# controller.net
KiCad netlist of a schematic drawn in Altium Designer
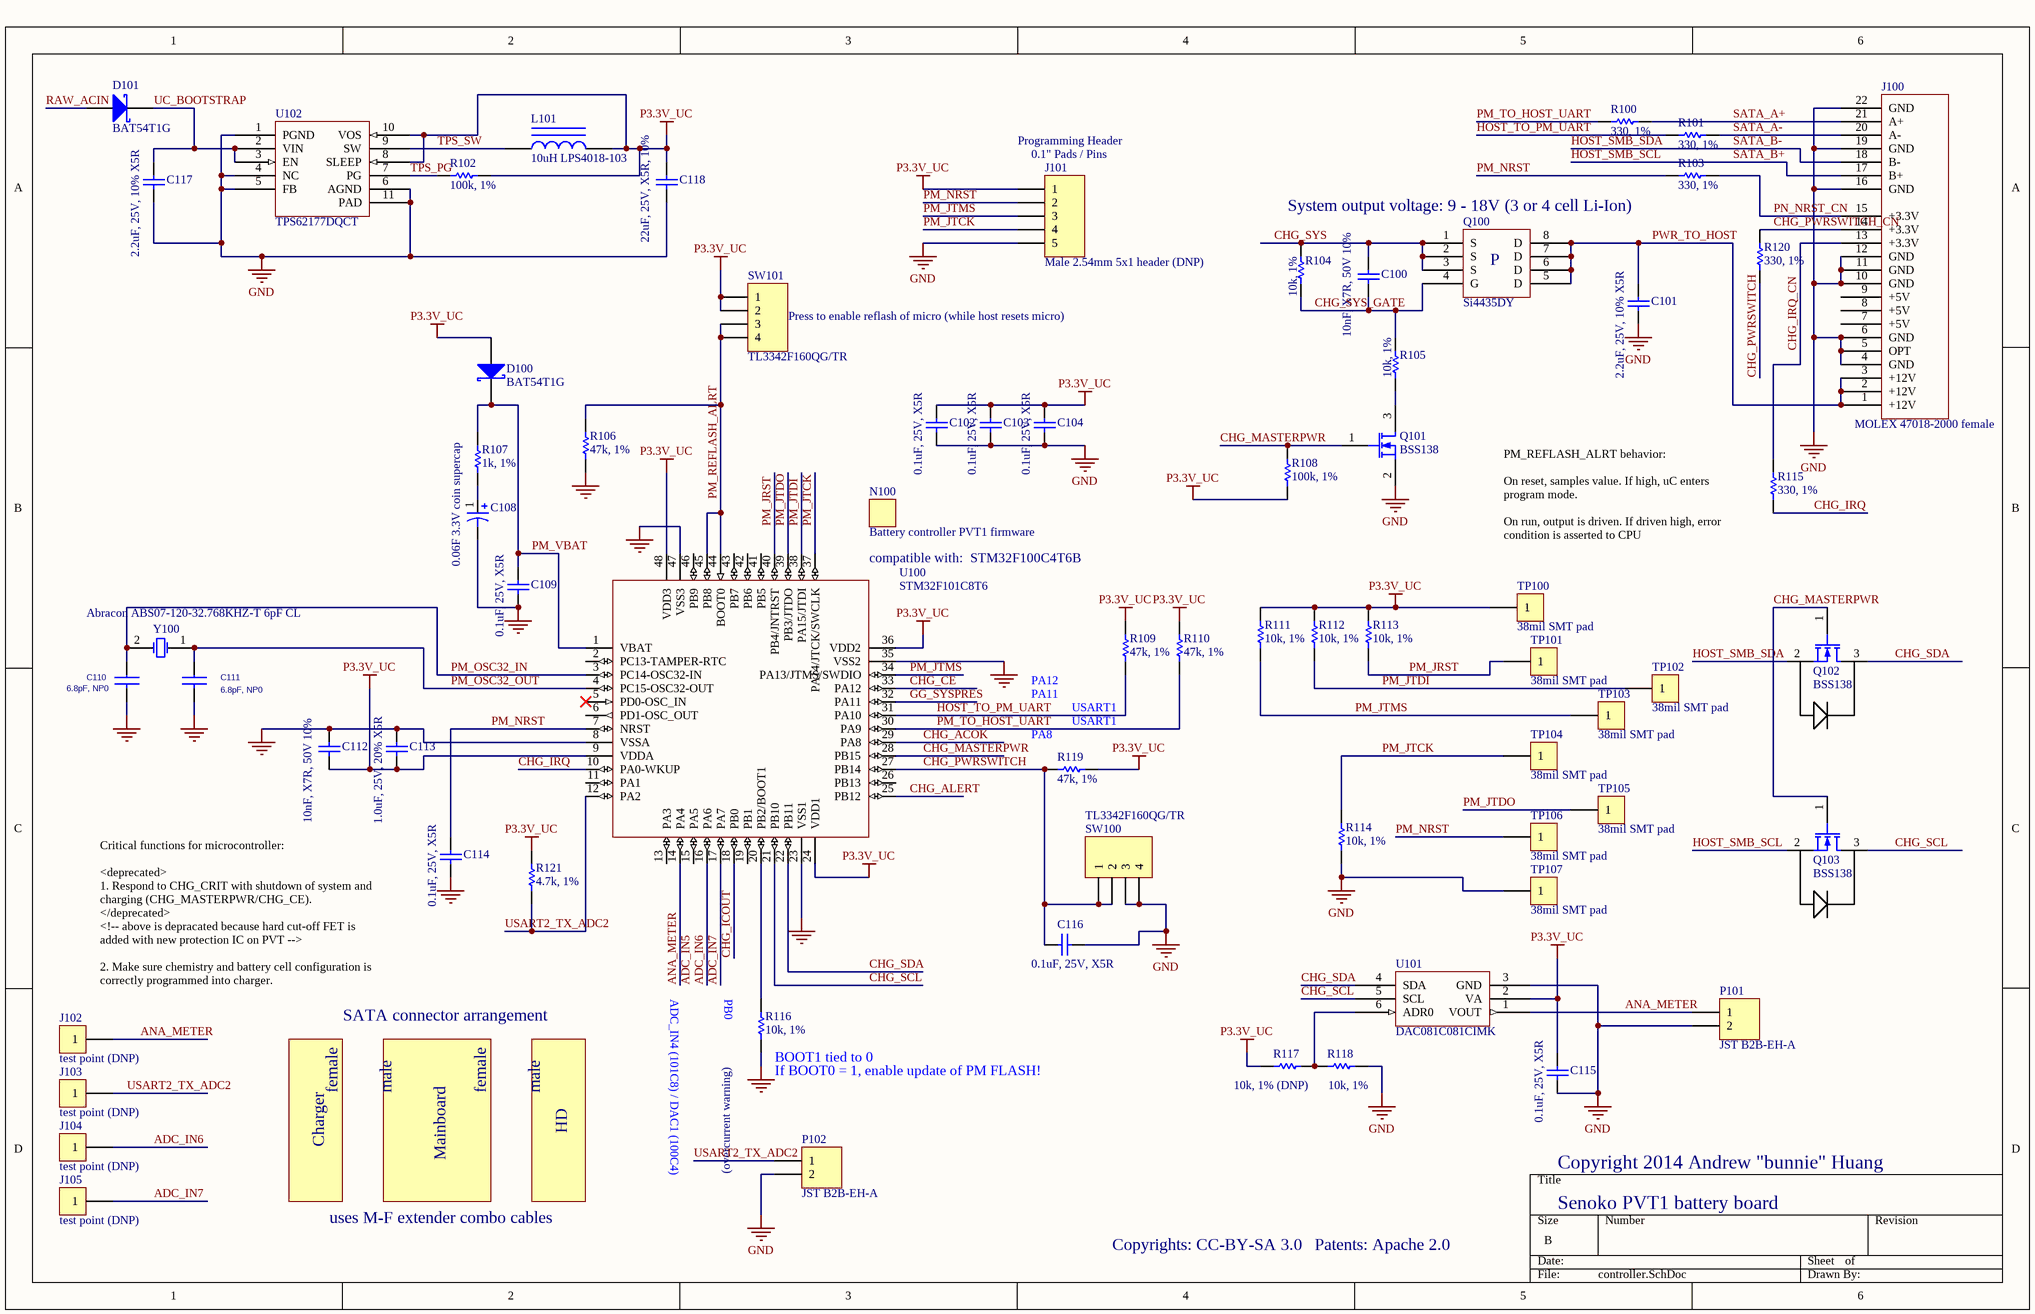
[diagram p0: controller.SchDoc]

(export (version "E")
  (design (tool "Eeschema 10.0.6"))
  (components
    (comp (ref "C100")
      (value "10nF, X7R, 50V 10%")
      (footprint "CAPC1005N")
      (description "Capacitor (Semiconductor SIM Model)")
      (fields (field (name "PUBLISHER") "Altium Limited"))
      (libsource (lib "Miscellaneous Devices") (part "Cap Semi"))
    )
    (comp (ref "C101")
      (value "2.2uF, 25V, 10% X5R")
      (footprint "CAPC1608N")
      (description "Capacitor (Semiconductor SIM Model)")
      (fields (field (name "PUBLISHER") "Altium Limited"))
      (libsource (lib "Miscellaneous Devices") (part "Cap Semi"))
    )
    (comp (ref "C102")
      (value "0.1uF, 25V, X5R")
      (footprint "CAPC1005N")
      (description "Capacitor (Semiconductor SIM Model)")
      (fields (field (name "PUBLISHER") "Altium Limited"))
      (libsource (lib "Miscellaneous Devices") (part "Cap Semi"))
    )
    (comp (ref "C103")
      (value "0.1uF, 25V, X5R")
      (footprint "CAPC1005N")
      (description "Capacitor (Semiconductor SIM Model)")
      (fields (field (name "PUBLISHER") "Altium Limited"))
      (libsource (lib "Miscellaneous Devices") (part "Cap Semi"))
    )
    (comp (ref "C104")
      (value "0.1uF, 25V, X5R")
      (footprint "CAPC1005N")
      (description "Capacitor (Semiconductor SIM Model)")
      (fields (field (name "PUBLISHER") "Altium Limited"))
      (libsource (lib "Miscellaneous Devices") (part "Cap Semi"))
    )
    (comp (ref "C108")
      (value "0.06F 3.3V coin supercap")
      (footprint "TAIYO_YUDEN_PAS414HR-VA5R")
      (description "Taiyo Yuden PAS414HR-VA5R")
      (fields (field (name "PUBLISHER") "Altium Limited"))
      (libsource (lib "Miscellaneous Devices") (part "Cap Pol3"))
    )
    (comp (ref "C109")
      (value "0.1uF, 25V, X5R")
      (footprint "CAPC1005N")
      (description "Capacitor (Semiconductor SIM Model)")
      (fields (field (name "PUBLISHER") "Altium Limited"))
      (libsource (lib "Miscellaneous Devices") (part "Cap Semi"))
    )
    (comp (ref "C110") (value "6.8pF, NP0") (libsource (lib "*") (part "CAP NP")))
    (comp (ref "C111") (value "6.8pF, NP0") (libsource (lib "*") (part "CAP NP")))
    (comp (ref "C112")
      (value "10nF, X7R, 50V 10%")
      (footprint "CAPC1005N")
      (description "Capacitor (Semiconductor SIM Model)")
      (fields (field (name "PUBLISHER") "Altium Limited"))
      (libsource (lib "Miscellaneous Devices") (part "Cap Semi"))
    )
    (comp (ref "C113")
      (value "1.0uF, 25V, 20% X5R")
      (footprint "CAPC1608N")
      (description "Capacitor (Semiconductor SIM Model)")
      (fields (field (name "PUBLISHER") "Altium Limited"))
      (libsource (lib "Miscellaneous Devices") (part "Cap Semi"))
    )
    (comp (ref "C114")
      (value "0.1uF, 25V, X5R")
      (footprint "CAPC1005N")
      (description "Capacitor (Semiconductor SIM Model)")
      (fields (field (name "PUBLISHER") "Altium Limited"))
      (libsource (lib "Miscellaneous Devices") (part "Cap Semi"))
    )
    (comp (ref "C115")
      (value "0.1uF, 25V, X5R")
      (footprint "CAPC1005N")
      (description "Capacitor (Semiconductor SIM Model)")
      (libsource (lib "Miscellaneous Devices") (part "Cap Semi"))
    )
    (comp (ref "C116")
      (value "0.1uF, 25V, X5R")
      (footprint "CAPC1005N")
      (description "Capacitor (Semiconductor SIM Model)")
      (fields (field (name "PUBLISHER") "Altium Limited"))
      (libsource (lib "Miscellaneous Devices") (part "Cap Semi"))
    )
    (comp (ref "C117")
      (value "2.2uF, 25V, 10% X5R")
      (footprint "CAPC1608N")
      (description "Capacitor (Semiconductor SIM Model)")
      (fields (field (name "PUBLISHER") "Altium Limited"))
      (libsource (lib "Miscellaneous Devices") (part "Cap Semi"))
    )
    (comp (ref "C118")
      (value "22uF, 25V, X5R, 10%")
      (footprint "CAPC3225N")
      (description "Capacitor (Semiconductor SIM Model)")
      (fields (field (name "PUBLISHER") "Altium Limited"))
      (libsource (lib "Miscellaneous Devices") (part "Cap Semi"))
    )
    (comp (ref "D100")
      (value "BAT54T1G")
      (footprint "SOD123")
      (description "Schottky Diode")
      (fields (field (name "PUBLISHER") "Altium Limited"))
      (libsource (lib "Miscellaneous Devices") (part "D Schottky"))
    )
    (comp (ref "D101")
      (value "BAT54T1G")
      (footprint "SOD123")
      (description "Schottky Diode")
      (fields (field (name "PUBLISHER") "Altium Limited"))
      (libsource (lib "Miscellaneous Devices") (part "D Schottky"))
    )
    (comp (ref "J100")
      (value "MOLEX 47018-2000 female")
      (footprint "SATA_MOLEX_47018_2000")
      (description "SATA+Power connector")
      (libsource (lib "commonsch") (part "SATA_22P_HEADER"))
    )
    (comp (ref "J101")
      (value "Male 2.54mm 5x1 header (DNP)")
      (footprint "HDR1X5")
      (description "Header, 5-Pin")
      (fields (field (name "PUBLISHER") "Altium Limited"))
      (libsource (lib "Miscellaneous Connectors") (part "Header 5"))
    )
    (comp (ref "J102")
      (value "test point (DNP)")
      (footprint "TP_SMT_38mil")
      (description "Connector")
      (libsource (lib "*") (part "CON1"))
    )
    (comp (ref "J103")
      (value "test point (DNP)")
      (footprint "TP_SMT_38mil")
      (description "Connector")
      (libsource (lib "*") (part "CON1"))
    )
    (comp (ref "J104")
      (value "test point (DNP)")
      (footprint "TP_SMT_38mil")
      (description "Connector")
      (libsource (lib "*") (part "CON1"))
    )
    (comp (ref "J105")
      (value "test point (DNP)")
      (footprint "TP_SMT_38mil")
      (description "Connector")
      (libsource (lib "*") (part "CON1"))
    )
    (comp (ref "L101")
      (value "10uH LPS4018-103")
      (footprint "COILCRAFT_LPS4018")
      (description "Magnetic-Core Inductor")
      (fields (field (name "PUBLISHER") "Altium Limited"))
      (libsource (lib "Miscellaneous Devices") (part "Inductor Iron"))
    )
    (comp (ref "N100")
      (value "Battery controller PVT1 firmware")
      (description "Placeholder for non-electrical BOM items")
      (libsource (lib "commonsch") (part "NOTE"))
    )
    (comp (ref "P101")
      (value "JST B2B-EH-A")
      (footprint "JST_B2B_EH_A")
      (description "Header, 2-Pin")
      (fields (field (name "PUBLISHER") "Altium Limited"))
      (libsource (lib "Miscellaneous Connectors") (part "Header 2"))
    )
    (comp (ref "P102")
      (value "JST B2B-EH-A")
      (footprint "JST_B2B_EH_A")
      (description "Header, 2-Pin")
      (fields (field (name "PUBLISHER") "Altium Limited"))
      (libsource (lib "Miscellaneous Connectors") (part "Header 2"))
    )
    (comp (ref "Q100")
      (value "Si4435DY")
      (footprint "SOIC127P600-8AN")
      (description "Singre P-channel FET, 8A, 30V")
      (libsource (lib "commonsch") (part "Si4435DY"))
    )
    (comp (ref "Q101")
      (value "BSS138")
      (footprint "SOT23-3N")
      (description "N-Channel MOSFET")
      (fields (field (name "PUBLISHER") "Altium Limited"))
      (libsource (lib "Miscellaneous Devices") (part "MOSFET-N"))
    )
    (comp (ref "Q102")
      (value "BSS138")
      (footprint "SOT23-3N")
      (description "N-Channel MOSFET")
      (fields (field (name "PUBLISHER") "Altium Limited"))
      (libsource (lib "Miscellaneous Devices") (part "MOSFET-N"))
    )
    (comp (ref "Q103")
      (value "BSS138")
      (footprint "SOT23-3N")
      (description "N-Channel MOSFET")
      (fields (field (name "PUBLISHER") "Altium Limited"))
      (libsource (lib "Miscellaneous Devices") (part "MOSFET-N"))
    )
    (comp (ref "R100")
      (value "330, 1%")
      (footprint "RESC1005N")
      (description "Resistor")
      (fields (field (name "PUBLISHER") "Altium Limited"))
      (libsource (lib "Miscellaneous Devices") (part "Res1"))
    )
    (comp (ref "R101")
      (value "330, 1%")
      (footprint "RESC1005N")
      (description "Resistor")
      (fields (field (name "PUBLISHER") "Altium Limited"))
      (libsource (lib "Miscellaneous Devices") (part "Res1"))
    )
    (comp (ref "R102")
      (value "100k, 1%")
      (footprint "RESC1005N")
      (description "Resistor")
      (fields (field (name "PUBLISHER") "Altium Limited"))
      (libsource (lib "Miscellaneous Devices") (part "Res1"))
    )
    (comp (ref "R103")
      (value "330, 1%")
      (footprint "RESC1005N")
      (description "Resistor")
      (fields (field (name "PUBLISHER") "Altium Limited"))
      (libsource (lib "Miscellaneous Devices") (part "Res1"))
    )
    (comp (ref "R104")
      (value "10k, 1%")
      (footprint "RESC1005N")
      (description "Resistor")
      (fields (field (name "PUBLISHER") "Altium Limited"))
      (libsource (lib "Miscellaneous Devices") (part "Res1"))
    )
    (comp (ref "R105")
      (value "10k, 1%")
      (footprint "RESC1005N")
      (description "Resistor")
      (fields (field (name "PUBLISHER") "Altium Limited"))
      (libsource (lib "Miscellaneous Devices") (part "Res1"))
    )
    (comp (ref "R106")
      (value "47k, 1%")
      (footprint "RESC1005N")
      (description "Resistor")
      (fields (field (name "PUBLISHER") "Altium Limited"))
      (libsource (lib "Miscellaneous Devices") (part "Res1"))
    )
    (comp (ref "R107")
      (value "1k, 1%")
      (footprint "RESC1005N")
      (description "Resistor")
      (fields (field (name "PUBLISHER") "Altium Limited"))
      (libsource (lib "Miscellaneous Devices") (part "Res1"))
    )
    (comp (ref "R108")
      (value "100k, 1%")
      (footprint "RESC1005N")
      (description "Resistor")
      (fields (field (name "PUBLISHER") "Altium Limited"))
      (libsource (lib "Miscellaneous Devices") (part "Res1"))
    )
    (comp (ref "R109")
      (value "47k, 1%")
      (footprint "RESC1005N")
      (description "Resistor")
      (fields (field (name "PUBLISHER") "Altium Limited"))
      (libsource (lib "Miscellaneous Devices") (part "Res1"))
    )
    (comp (ref "R110")
      (value "47k, 1%")
      (footprint "RESC1005N")
      (description "Resistor")
      (fields (field (name "PUBLISHER") "Altium Limited"))
      (libsource (lib "Miscellaneous Devices") (part "Res1"))
    )
    (comp (ref "R111")
      (value "10k, 1%")
      (footprint "RESC1005N")
      (description "Resistor")
      (fields (field (name "PUBLISHER") "Altium Limited"))
      (libsource (lib "Miscellaneous Devices") (part "Res1"))
    )
    (comp (ref "R112")
      (value "10k, 1%")
      (footprint "RESC1005N")
      (description "Resistor")
      (fields (field (name "PUBLISHER") "Altium Limited"))
      (libsource (lib "Miscellaneous Devices") (part "Res1"))
    )
    (comp (ref "R113")
      (value "10k, 1%")
      (footprint "RESC1005N")
      (description "Resistor")
      (fields (field (name "PUBLISHER") "Altium Limited"))
      (libsource (lib "Miscellaneous Devices") (part "Res1"))
    )
    (comp (ref "R114")
      (value "10k, 1%")
      (footprint "RESC1005N")
      (description "Resistor")
      (fields (field (name "PUBLISHER") "Altium Limited"))
      (libsource (lib "Miscellaneous Devices") (part "Res1"))
    )
    (comp (ref "R115")
      (value "330, 1%")
      (footprint "RESC1005N")
      (description "Resistor")
      (fields (field (name "PUBLISHER") "Altium Limited"))
      (libsource (lib "Miscellaneous Devices") (part "Res1"))
    )
    (comp (ref "R116")
      (value "10k, 1%")
      (footprint "RESC1005N")
      (description "Resistor")
      (fields (field (name "PUBLISHER") "Altium Limited"))
      (libsource (lib "Miscellaneous Devices") (part "Res1"))
    )
    (comp (ref "R117")
      (value "10k, 1% (DNP)")
      (footprint "RESC1005N")
      (description "Resistor")
      (fields (field (name "PUBLISHER") "Altium Limited"))
      (libsource (lib "Miscellaneous Devices") (part "Res1"))
    )
    (comp (ref "R118")
      (value "10k, 1%")
      (footprint "RESC1005N")
      (description "Resistor")
      (fields (field (name "PUBLISHER") "Altium Limited"))
      (libsource (lib "Miscellaneous Devices") (part "Res1"))
    )
    (comp (ref "R119")
      (value "47k, 1%")
      (footprint "RESC1005N")
      (description "Resistor")
      (fields (field (name "PUBLISHER") "Altium Limited"))
      (libsource (lib "Miscellaneous Devices") (part "Res1"))
    )
    (comp (ref "R120")
      (value "330, 1%")
      (footprint "RESC1005N")
      (description "Resistor")
      (fields (field (name "PUBLISHER") "Altium Limited"))
      (libsource (lib "Miscellaneous Devices") (part "Res1"))
    )
    (comp (ref "R121")
      (value "4.7k, 1%")
      (footprint "RESC1005N")
      (description "Resistor")
      (fields (field (name "PUBLISHER") "Altium Limited"))
      (libsource (lib "Miscellaneous Devices") (part "Res1"))
    )
    (comp (ref "SW100")
      (value "TL3342F160QG/TR")
      (footprint "SWITCH_TS-1187A")
      (description "Chi Fung TS-1187A")
      (fields (field (name "PUBLISHER") "Altium Limited"))
      (libsource (lib "Miscellaneous Connectors") (part "Header 4"))
    )
    (comp (ref "SW101")
      (value "TL3342F160QG/TR")
      (footprint "SWITCH_TS-1187A")
      (description "Chi Fung TS-1187A")
      (fields (field (name "PUBLISHER") "Altium Limited"))
      (libsource (lib "") (part "Header 4_1"))
    )
    (comp (ref "TP100")
      (value "38mil SMT pad")
      (footprint "TP_SMT_38mil")
      (description "Connector")
      (libsource (lib "") (part "CON1_1"))
    )
    (comp (ref "TP101")
      (value "38mil SMT pad")
      (footprint "TP_SMT_38mil")
      (description "Connector")
      (libsource (lib "") (part "CON1_1"))
    )
    (comp (ref "TP102")
      (value "38mil SMT pad")
      (footprint "TP_SMT_38mil")
      (description "Connector")
      (libsource (lib "") (part "CON1_1"))
    )
    (comp (ref "TP103")
      (value "38mil SMT pad")
      (footprint "TP_SMT_38mil")
      (description "Connector")
      (libsource (lib "") (part "CON1_1"))
    )
    (comp (ref "TP104")
      (value "38mil SMT pad")
      (footprint "TP_SMT_38mil")
      (description "Connector")
      (libsource (lib "") (part "CON1_1"))
    )
    (comp (ref "TP105")
      (value "38mil SMT pad")
      (footprint "TP_SMT_38mil")
      (description "Connector")
      (libsource (lib "") (part "CON1_1"))
    )
    (comp (ref "TP106")
      (value "38mil SMT pad")
      (footprint "TP_SMT_38mil")
      (description "Connector")
      (libsource (lib "") (part "CON1_1"))
    )
    (comp (ref "TP107")
      (value "38mil SMT pad")
      (footprint "TP_SMT_38mil")
      (description "Connector")
      (libsource (lib "") (part "CON1_1"))
    )
    (comp (ref "U100")
      (value "STM32F101C8T6")
      (footprint "TSQFP50P900X900-48N")
      (description "32-bit ARM Coretex high performance microcontroller")
      (libsource (lib "*") (part "STM32F103C8T6"))
    )
    (comp (ref "U101")
      (value "DAC081C081CIMK")
      (footprint "SOT26A-6N")
      (description "Single 8-bit DAC for I2C bus")
      (libsource (lib "commonsch") (part "DAC081C81CIMK"))
    )
    (comp (ref "U102")
      (value "TPS62177DQCT")
      (footprint "TI_DQC_R_PWSON_N10")
      (description "28V, 0.5A step-down converter with sleep mode")
      (libsource (lib "commonsch") (part "TPS62177DQCT"))
    )
    (comp (ref "Y100")
      (value "Abracon ABS07-120-32.768KHZ-T 6pF CL")
      (footprint "ABS07-120")
      (description "Crystal Oscillator")
      (fields (field (name "PUBLISHER") "Altium Limited"))
      (libsource (lib "Miscellaneous Devices") (part "XTAL"))
    )
  )
  (nets
    (net (code "2") (name "/ADC_IN6") (class "Default")
      (node (ref "J104") (pin "1") (pinfunction "1_1") (pintype "passive"))
      (node (ref "U100") (pin "16") (pinfunction "PA6_16") (pintype "bidirectional"))
    )
    (net (code "3") (name "/ADC_IN7") (class "Default")
      (node (ref "J105") (pin "1") (pinfunction "1_1") (pintype "passive"))
      (node (ref "U100") (pin "17") (pinfunction "PA7_17") (pintype "bidirectional"))
    )
    (net (code "4") (name "/ANA_METER") (class "Default")
      (node (ref "J102") (pin "1") (pinfunction "1_1") (pintype "passive"))
      (node (ref "P101") (pin "1") (pinfunction "1_1") (pintype "passive"))
      (node (ref "U100") (pin "14") (pinfunction "PA4_14") (pintype "bidirectional"))
      (node (ref "U101") (pin "1") (pinfunction "VOUT_1") (pintype "output"))
    )
    (net (code "5") (name "/CHG_ACOK") (class "Default")
      (node (ref "U100") (pin "29") (pinfunction "PA8_29") (pintype "bidirectional"))
    )
    (net (code "6") (name "/CHG_ALERT") (class "Default")
      (node (ref "U100") (pin "25") (pinfunction "PB12_25") (pintype "bidirectional"))
    )
    (net (code "7") (name "/CHG_CE") (class "Default")
      (node (ref "U100") (pin "33") (pinfunction "PA12_33") (pintype "bidirectional"))
    )
    (net (code "8") (name "/CHG_ICOUT") (class "Default")
      (node (ref "U100") (pin "18") (pinfunction "PB0_18") (pintype "bidirectional"))
    )
    (net (code "9") (name "/CHG_IRQ") (class "Default")
      (node (ref "R115") (pin "1") (pinfunction "1_1") (pintype "passive"))
      (node (ref "U100") (pin "10") (pinfunction "PA0-WKUP_10") (pintype "bidirectional"))
    )
    (net (code "10") (name "/CHG_IRQ_CN") (class "Default")
      (node (ref "J100") (pin "13") (pinfunction "+3.3V_13") (pintype "power_in"))
      (node (ref "R115") (pin "2") (pinfunction "2_2") (pintype "passive"))
    )
    (net (code "11") (name "/CHG_MASTERPWR") (class "Default")
      (node (ref "Q101") (pin "1") (pinfunction "G_1") (pintype "passive"))
      (node (ref "Q102") (pin "1") (pinfunction "G_1") (pintype "passive"))
      (node (ref "Q103") (pin "1") (pinfunction "G_1") (pintype "passive"))
      (node (ref "R108") (pin "2") (pinfunction "2_2") (pintype "passive"))
      (node (ref "U100") (pin "28") (pinfunction "PB15_28") (pintype "bidirectional"))
    )
    (net (code "12") (name "/CHG_PWRSWITCH") (class "Default")
      (node (ref "C116") (pin "2") (pinfunction "2_2") (pintype "passive"))
      (node (ref "R119") (pin "1") (pinfunction "1_1") (pintype "passive"))
      (node (ref "R120") (pin "1") (pinfunction "1_1") (pintype "passive"))
      (node (ref "SW100") (pin "1") (pinfunction "1_1") (pintype "passive"))
      (node (ref "SW100") (pin "2") (pinfunction "2_2") (pintype "passive"))
      (node (ref "U100") (pin "27") (pinfunction "PB14_27") (pintype "bidirectional"))
    )
    (net (code "13") (name "/CHG_PWRSWITCH_CN") (class "Default")
      (node (ref "J100") (pin "14") (pinfunction "+3.3V_14") (pintype "power_in"))
      (node (ref "R120") (pin "2") (pinfunction "2_2") (pintype "passive"))
    )
    (net (code "14") (name "/CHG_SCL") (class "Default")
      (node (ref "Q103") (pin "3") (pinfunction "D_3") (pintype "passive"))
      (node (ref "U100") (pin "21") (pinfunction "PB10_21") (pintype "bidirectional"))
      (node (ref "U101") (pin "5") (pinfunction "SCL_5") (pintype "open_collector"))
    )
    (net (code "15") (name "/CHG_SDA") (class "Default")
      (node (ref "Q102") (pin "3") (pinfunction "D_3") (pintype "passive"))
      (node (ref "U100") (pin "22") (pinfunction "PB11_22") (pintype "bidirectional"))
      (node (ref "U101") (pin "4") (pinfunction "SDA_4") (pintype "open_collector"))
    )
    (net (code "16") (name "/CHG_SYS") (class "Default")
      (node (ref "C100") (pin "1") (pinfunction "1_1") (pintype "passive"))
      (node (ref "Q100") (pin "1") (pinfunction "S_1") (pintype "passive"))
      (node (ref "Q100") (pin "2") (pinfunction "S_2") (pintype "passive"))
      (node (ref "Q100") (pin "3") (pinfunction "S_3") (pintype "passive"))
      (node (ref "R104") (pin "2") (pinfunction "2_2") (pintype "passive"))
    )
    (net (code "17") (name "/CHG_SYS_GATE") (class "Default")
      (node (ref "C100") (pin "2") (pinfunction "2_2") (pintype "passive"))
      (node (ref "Q100") (pin "4") (pinfunction "G_4") (pintype "passive"))
      (node (ref "R104") (pin "1") (pinfunction "1_1") (pintype "passive"))
      (node (ref "R105") (pin "2") (pinfunction "2_2") (pintype "passive"))
    )
    (net (code "18") (name "/GG_SYSPRES") (class "Default")
      (node (ref "U100") (pin "32") (pinfunction "PA11_32") (pintype "bidirectional"))
    )
    (net (code "19") (name "/HOST_SMB_SCL") (class "Default")
      (node (ref "J100") (pin "17") (pinfunction "B+_17") (pintype "passive"))
      (node (ref "Q103") (pin "2") (pinfunction "S_2") (pintype "passive"))
    )
    (net (code "20") (name "/HOST_SMB_SDA") (class "Default")
      (node (ref "J100") (pin "18") (pinfunction "B-_18") (pintype "passive"))
      (node (ref "Q102") (pin "2") (pinfunction "S_2") (pintype "passive"))
    )
    (net (code "21") (name "/HOST_TO_PM_UART") (class "Default")
      (node (ref "R101") (pin "1") (pinfunction "1_1") (pintype "passive"))
      (node (ref "R109") (pin "1") (pinfunction "1_1") (pintype "passive"))
      (node (ref "U100") (pin "31") (pinfunction "PA10_31") (pintype "bidirectional"))
    )
    (net (code "22") (name "/PM_JRST") (class "Default")
      (node (ref "R113") (pin "1") (pinfunction "1_1") (pintype "passive"))
      (node (ref "TP101") (pin "1") (pinfunction "1_1") (pintype "passive"))
      (node (ref "U100") (pin "40") (pinfunction "PB4/JNTRST_40") (pintype "bidirectional"))
    )
    (net (code "23") (name "/PM_JTCK") (class "Default")
      (node (ref "J101") (pin "4") (pinfunction "4_4") (pintype "passive"))
      (node (ref "R114") (pin "2") (pinfunction "2_2") (pintype "passive"))
      (node (ref "TP104") (pin "1") (pinfunction "1_1") (pintype "passive"))
      (node (ref "U100") (pin "37") (pinfunction "PA14/JTCK/SWCLK_37") (pintype "bidirectional"))
    )
    (net (code "24") (name "/PM_JTDI") (class "Default")
      (node (ref "R112") (pin "1") (pinfunction "1_1") (pintype "passive"))
      (node (ref "TP102") (pin "1") (pinfunction "1_1") (pintype "passive"))
      (node (ref "U100") (pin "38") (pinfunction "PA15/JTDI_38") (pintype "bidirectional"))
    )
    (net (code "25") (name "/PM_JTDO") (class "Default")
      (node (ref "TP105") (pin "1") (pinfunction "1_1") (pintype "passive"))
      (node (ref "U100") (pin "39") (pinfunction "PB3/JTDO_39") (pintype "bidirectional"))
    )
    (net (code "26") (name "/PM_JTMS") (class "Default")
      (node (ref "J101") (pin "3") (pinfunction "3_3") (pintype "passive"))
      (node (ref "R111") (pin "1") (pinfunction "1_1") (pintype "passive"))
      (node (ref "TP103") (pin "1") (pinfunction "1_1") (pintype "passive"))
      (node (ref "U100") (pin "34") (pinfunction "PA13/JTMS/SWDIO_34") (pintype "bidirectional"))
    )
    (net (code "27") (name "/PM_NRST") (class "Default")
      (node (ref "C114") (pin "1") (pinfunction "1_1") (pintype "passive"))
      (node (ref "J101") (pin "2") (pinfunction "2_2") (pintype "passive"))
      (node (ref "R103") (pin "1") (pinfunction "1_1") (pintype "passive"))
      (node (ref "TP106") (pin "1") (pinfunction "1_1") (pintype "passive"))
      (node (ref "U100") (pin "7") (pinfunction "NRST_7") (pintype "bidirectional"))
    )
    (net (code "28") (name "/PM_OSC32_IN") (class "Default")
      (node (ref "C110") (pin "1") (pinfunction "1_1") (pintype "passive"))
      (node (ref "U100") (pin "3") (pinfunction "PC14-OSC32-IN_3") (pintype "bidirectional"))
      (node (ref "Y100") (pin "2") (pinfunction "OSC2_2") (pintype "passive"))
    )
    (net (code "29") (name "/PM_OSC32_OUT") (class "Default")
      (node (ref "C111") (pin "1") (pinfunction "1_1") (pintype "passive"))
      (node (ref "U100") (pin "4") (pinfunction "PC15-OSC32-OUT_4") (pintype "bidirectional"))
      (node (ref "Y100") (pin "1") (pinfunction "OSC1_1") (pintype "passive"))
    )
    (net (code "30") (name "/PM_REFLASH_ALRT") (class "Default")
      (node (ref "R106") (pin "2") (pinfunction "2_2") (pintype "passive"))
      (node (ref "SW101") (pin "3") (pinfunction "3_3") (pintype "passive"))
      (node (ref "SW101") (pin "4") (pinfunction "4_4") (pintype "passive"))
      (node (ref "U100") (pin "44") (pinfunction "BOOT0_44") (pintype "input"))
      (node (ref "U100") (pin "45") (pinfunction "PB8_45") (pintype "bidirectional"))
    )
    (net (code "31") (name "/PM_TO_HOST_UART") (class "Default")
      (node (ref "R100") (pin "1") (pinfunction "1_1") (pintype "passive"))
      (node (ref "R110") (pin "1") (pinfunction "1_1") (pintype "passive"))
      (node (ref "U100") (pin "30") (pinfunction "PA9_30") (pintype "bidirectional"))
    )
    (net (code "32") (name "/PM_VBAT") (class "Default")
      (node (ref "C109") (pin "1") (pinfunction "1_1") (pintype "passive"))
      (node (ref "D100") (pin "2") (pinfunction "K_2") (pintype "passive"))
      (node (ref "R107") (pin "2") (pinfunction "2_2") (pintype "passive"))
      (node (ref "U100") (pin "1") (pinfunction "VBAT_1") (pintype "power_in"))
    )
    (net (code "33") (name "/PN_NRST_CN") (class "Default")
      (node (ref "J100") (pin "15") (pinfunction "+3.3V_15") (pintype "power_in"))
      (node (ref "R103") (pin "2") (pinfunction "2_2") (pintype "passive"))
    )
    (net (code "34") (name "/PWR_TO_HOST") (class "Default")
      (node (ref "C101") (pin "1") (pinfunction "1_1") (pintype "passive"))
      (node (ref "J100") (pin "1") (pinfunction "+12V_1") (pintype "power_in"))
      (node (ref "J100") (pin "2") (pinfunction "+12V_2") (pintype "power_in"))
      (node (ref "J100") (pin "3") (pinfunction "+12V_3") (pintype "power_in"))
      (node (ref "Q100") (pin "5") (pinfunction "D_5") (pintype "passive"))
      (node (ref "Q100") (pin "6") (pinfunction "D_6") (pintype "passive"))
      (node (ref "Q100") (pin "7") (pinfunction "D_7") (pintype "passive"))
      (node (ref "Q100") (pin "8") (pinfunction "D_8") (pintype "passive"))
    )
    (net (code "35") (name "/RAW_ACIN") (class "Default")
      (node (ref "D101") (pin "1") (pinfunction "A_1") (pintype "passive"))
    )
    (net (code "36") (name "/SATA_A+") (class "Default")
      (node (ref "J100") (pin "21") (pinfunction "A+_21") (pintype "passive"))
      (node (ref "R100") (pin "2") (pinfunction "2_2") (pintype "passive"))
    )
    (net (code "37") (name "/SATA_A-") (class "Default")
      (node (ref "J100") (pin "20") (pinfunction "A-_20") (pintype "passive"))
      (node (ref "R101") (pin "2") (pinfunction "2_2") (pintype "passive"))
    )
    (net (code "38") (name "/TPS_PG") (class "Default")
      (node (ref "R102") (pin "2") (pinfunction "2_2") (pintype "passive"))
      (node (ref "U102") (pin "7") (pinfunction "PG_7") (pintype "open_collector"))
    )
    (net (code "39") (name "/TPS_SW") (class "Default")
      (node (ref "L101") (pin "1") (pinfunction "1_1") (pintype "passive"))
      (node (ref "U102") (pin "9") (pinfunction "SW_9") (pintype "passive"))
    )
    (net (code "40") (name "/UC_BOOTSTRAP") (class "Default")
      (node (ref "C117") (pin "1") (pinfunction "1_1") (pintype "passive"))
      (node (ref "D101") (pin "2") (pinfunction "K_2") (pintype "passive"))
      (node (ref "U102") (pin "2") (pinfunction "VIN_2") (pintype "power_in"))
      (node (ref "U102") (pin "3") (pinfunction "EN_3") (pintype "input"))
    )
    (net (code "41") (name "/USART2_TX_ADC2") (class "Default")
      (node (ref "J103") (pin "1") (pinfunction "1_1") (pintype "passive"))
      (node (ref "P102") (pin "1") (pinfunction "1_1") (pintype "passive"))
      (node (ref "R121") (pin "1") (pinfunction "1_1") (pintype "passive"))
      (node (ref "U100") (pin "12") (pinfunction "PA2_12") (pintype "bidirectional"))
    )
    (net (code "42") (name "GND") (class "Default")
      (node (ref "C101") (pin "2") (pinfunction "2_2") (pintype "passive"))
      (node (ref "C102") (pin "2") (pinfunction "2_2") (pintype "passive"))
      (node (ref "C103") (pin "2") (pinfunction "2_2") (pintype "passive"))
      (node (ref "C104") (pin "2") (pinfunction "2_2") (pintype "passive"))
      (node (ref "C108") (pin "2") (pinfunction "2_2") (pintype "passive"))
      (node (ref "C109") (pin "2") (pinfunction "2_2") (pintype "passive"))
      (node (ref "C110") (pin "2") (pinfunction "2_2") (pintype "passive"))
      (node (ref "C111") (pin "2") (pinfunction "2_2") (pintype "passive"))
      (node (ref "C112") (pin "1") (pinfunction "1_1") (pintype "passive"))
      (node (ref "C113") (pin "1") (pinfunction "1_1") (pintype "passive"))
      (node (ref "C114") (pin "2") (pinfunction "2_2") (pintype "passive"))
      (node (ref "C115") (pin "2") (pinfunction "2_2") (pintype "passive"))
      (node (ref "C116") (pin "1") (pinfunction "1_1") (pintype "passive"))
      (node (ref "C117") (pin "2") (pinfunction "2_2") (pintype "passive"))
      (node (ref "C118") (pin "2") (pinfunction "2_2") (pintype "passive"))
      (node (ref "J100") (pin "10") (pinfunction "GND_10") (pintype "power_in"))
      (node (ref "J100") (pin "11") (pinfunction "GND_11") (pintype "power_in"))
      (node (ref "J100") (pin "12") (pinfunction "GND_12") (pintype "power_in"))
      (node (ref "J100") (pin "16") (pinfunction "GND_16") (pintype "power_in"))
      (node (ref "J100") (pin "19") (pinfunction "GND_19") (pintype "power_in"))
      (node (ref "J100") (pin "22") (pinfunction "GND_22") (pintype "power_in"))
      (node (ref "J100") (pin "4") (pinfunction "GND_4") (pintype "power_in"))
      (node (ref "J100") (pin "5") (pinfunction "OPT_5") (pintype "passive"))
      (node (ref "J100") (pin "6") (pinfunction "GND_6") (pintype "power_in"))
      (node (ref "J101") (pin "5") (pinfunction "5_5") (pintype "passive"))
      (node (ref "P101") (pin "2") (pinfunction "2_2") (pintype "passive"))
      (node (ref "P102") (pin "2") (pinfunction "2_2") (pintype "passive"))
      (node (ref "Q101") (pin "2") (pinfunction "S_2") (pintype "passive"))
      (node (ref "R106") (pin "1") (pinfunction "1_1") (pintype "passive"))
      (node (ref "R114") (pin "1") (pinfunction "1_1") (pintype "passive"))
      (node (ref "R116") (pin "1") (pinfunction "1_1") (pintype "passive"))
      (node (ref "R118") (pin "2") (pinfunction "2_2") (pintype "passive"))
      (node (ref "SW100") (pin "3") (pinfunction "3_3") (pintype "passive"))
      (node (ref "SW100") (pin "4") (pinfunction "4_4") (pintype "passive"))
      (node (ref "TP107") (pin "1") (pinfunction "1_1") (pintype "passive"))
      (node (ref "U100") (pin "23") (pinfunction "VSS1_23") (pintype "power_in"))
      (node (ref "U100") (pin "35") (pinfunction "VSS2_35") (pintype "power_in"))
      (node (ref "U100") (pin "47") (pinfunction "VSS3_47") (pintype "power_in"))
      (node (ref "U100") (pin "8") (pinfunction "VSSA_8") (pintype "power_in"))
      (node (ref "U101") (pin "3") (pinfunction "GND_3") (pintype "power_in"))
      (node (ref "U102") (pin "1") (pinfunction "PGND_1") (pintype "power_in"))
      (node (ref "U102") (pin "11") (pinfunction "PAD_11") (pintype "power_in"))
      (node (ref "U102") (pin "4") (pinfunction "NC_4") (pintype "passive"))
      (node (ref "U102") (pin "5") (pinfunction "FB_5") (pintype "passive"))
      (node (ref "U102") (pin "6") (pinfunction "AGND_6") (pintype "power_in"))
    )
    (net (code "43") (name "Net-(C108-Pad1)") (class "Default")
      (node (ref "C108") (pin "1") (pinfunction "1_1") (pintype "passive"))
      (node (ref "R107") (pin "1") (pinfunction "1_1") (pintype "passive"))
    )
    (net (code "44") (name "Net-(Q101-D)") (class "Default")
      (node (ref "Q101") (pin "3") (pinfunction "D_3") (pintype "passive"))
      (node (ref "R105") (pin "1") (pinfunction "1_1") (pintype "passive"))
    )
    (net (code "45") (name "Net-(U100-PB2{slash}BOOT1)") (class "Default")
      (node (ref "R116") (pin "2") (pinfunction "2_2") (pintype "passive"))
      (node (ref "U100") (pin "20") (pinfunction "PB2/BOOT1_20") (pintype "bidirectional"))
    )
    (net (code "46") (name "Net-(U101-ADR0)") (class "Default")
      (node (ref "R117") (pin "2") (pinfunction "2_2") (pintype "passive"))
      (node (ref "R118") (pin "1") (pinfunction "1_1") (pintype "passive"))
      (node (ref "U101") (pin "6") (pinfunction "ADR0_6") (pintype "input"))
    )
    (net (code "47") (name "P3.3V_UC") (class "Default")
      (node (ref "C102") (pin "1") (pinfunction "1_1") (pintype "passive"))
      (node (ref "C103") (pin "1") (pinfunction "1_1") (pintype "passive"))
      (node (ref "C104") (pin "1") (pinfunction "1_1") (pintype "passive"))
      (node (ref "C112") (pin "2") (pinfunction "2_2") (pintype "passive"))
      (node (ref "C113") (pin "2") (pinfunction "2_2") (pintype "passive"))
      (node (ref "C115") (pin "1") (pinfunction "1_1") (pintype "passive"))
      (node (ref "C118") (pin "1") (pinfunction "1_1") (pintype "passive"))
      (node (ref "D100") (pin "1") (pinfunction "A_1") (pintype "passive"))
      (node (ref "J101") (pin "1") (pinfunction "1_1") (pintype "passive"))
      (node (ref "L101") (pin "2") (pinfunction "2_2") (pintype "passive"))
      (node (ref "R102") (pin "1") (pinfunction "1_1") (pintype "passive"))
      (node (ref "R108") (pin "1") (pinfunction "1_1") (pintype "passive"))
      (node (ref "R109") (pin "2") (pinfunction "2_2") (pintype "passive"))
      (node (ref "R110") (pin "2") (pinfunction "2_2") (pintype "passive"))
      (node (ref "R111") (pin "2") (pinfunction "2_2") (pintype "passive"))
      (node (ref "R112") (pin "2") (pinfunction "2_2") (pintype "passive"))
      (node (ref "R113") (pin "2") (pinfunction "2_2") (pintype "passive"))
      (node (ref "R117") (pin "1") (pinfunction "1_1") (pintype "passive"))
      (node (ref "R119") (pin "2") (pinfunction "2_2") (pintype "passive"))
      (node (ref "R121") (pin "2") (pinfunction "2_2") (pintype "passive"))
      (node (ref "SW101") (pin "1") (pinfunction "1_1") (pintype "passive"))
      (node (ref "SW101") (pin "2") (pinfunction "2_2") (pintype "passive"))
      (node (ref "TP100") (pin "1") (pinfunction "1_1") (pintype "passive"))
      (node (ref "U100") (pin "24") (pinfunction "VDD1_24") (pintype "power_in"))
      (node (ref "U100") (pin "36") (pinfunction "VDD2_36") (pintype "power_in"))
      (node (ref "U100") (pin "48") (pinfunction "VDD3_48") (pintype "power_in"))
      (node (ref "U100") (pin "9") (pinfunction "VDDA_9") (pintype "power_in"))
      (node (ref "U101") (pin "2") (pinfunction "VA_2") (pintype "power_in"))
      (node (ref "U102") (pin "10") (pinfunction "VOS_10") (pintype "input"))
      (node (ref "U102") (pin "8") (pinfunction "SLEEP_8") (pintype "input"))
    )
    (net (code "48") (name "unconnected-(J100-+5V-Pad7)") (class "Default")
      (node (ref "J100") (pin "7") (pinfunction "+5V_7") (pintype "power_in"))
    )
    (net (code "49") (name "unconnected-(J100-+5V-Pad8)") (class "Default")
      (node (ref "J100") (pin "8") (pinfunction "+5V_8") (pintype "power_in"))
    )
    (net (code "50") (name "unconnected-(J100-+5V-Pad9)") (class "Default")
      (node (ref "J100") (pin "9") (pinfunction "+5V_9") (pintype "power_in"))
    )
    (net (code "51") (name "unconnected-(U100-PA1-Pad11)") (class "Default")
      (node (ref "U100") (pin "11") (pinfunction "PA1_11") (pintype "bidirectional"))
    )
    (net (code "52") (name "unconnected-(U100-PA3-Pad13)") (class "Default")
      (node (ref "U100") (pin "13") (pinfunction "PA3_13") (pintype "bidirectional"))
    )
    (net (code "53") (name "unconnected-(U100-PA5-Pad15)") (class "Default")
      (node (ref "U100") (pin "15") (pinfunction "PA5_15") (pintype "bidirectional"))
    )
    (net (code "54") (name "unconnected-(U100-PB1-Pad19)") (class "Default")
      (node (ref "U100") (pin "19") (pinfunction "PB1_19") (pintype "bidirectional"))
    )
    (net (code "55") (name "unconnected-(U100-PB5-Pad41)") (class "Default")
      (node (ref "U100") (pin "41") (pinfunction "PB5_41") (pintype "bidirectional"))
    )
    (net (code "56") (name "unconnected-(U100-PB6-Pad42)") (class "Default")
      (node (ref "U100") (pin "42") (pinfunction "PB6_42") (pintype "bidirectional"))
    )
    (net (code "57") (name "unconnected-(U100-PB7-Pad43)") (class "Default")
      (node (ref "U100") (pin "43") (pinfunction "PB7_43") (pintype "bidirectional"))
    )
    (net (code "58") (name "unconnected-(U100-PB9-Pad46)") (class "Default")
      (node (ref "U100") (pin "46") (pinfunction "PB9_46") (pintype "bidirectional"))
    )
    (net (code "59") (name "unconnected-(U100-PB13-Pad26)") (class "Default")
      (node (ref "U100") (pin "26") (pinfunction "PB13_26") (pintype "bidirectional"))
    )
    (net (code "60") (name "unconnected-(U100-PC13-TAMPER-RTC-Pad2)") (class "Default")
      (node (ref "U100") (pin "2") (pinfunction "PC13-TAMPER-RTC_2") (pintype "bidirectional"))
    )
    (net (code "61") (name "unconnected-(U100-PD0-OSC_IN-Pad5)") (class "Default")
      (node (ref "U100") (pin "5") (pinfunction "PD0-OSC_IN_5") (pintype "input+no_connect"))
    )
    (net (code "62") (name "unconnected-(U100-PD1-OSC_OUT-Pad6)") (class "Default")
      (node (ref "U100") (pin "6") (pinfunction "PD1-OSC_OUT_6") (pintype "output"))
    )
  )
)
